# io2.net
KiCad netlist of a schematic drawn in EAGLE
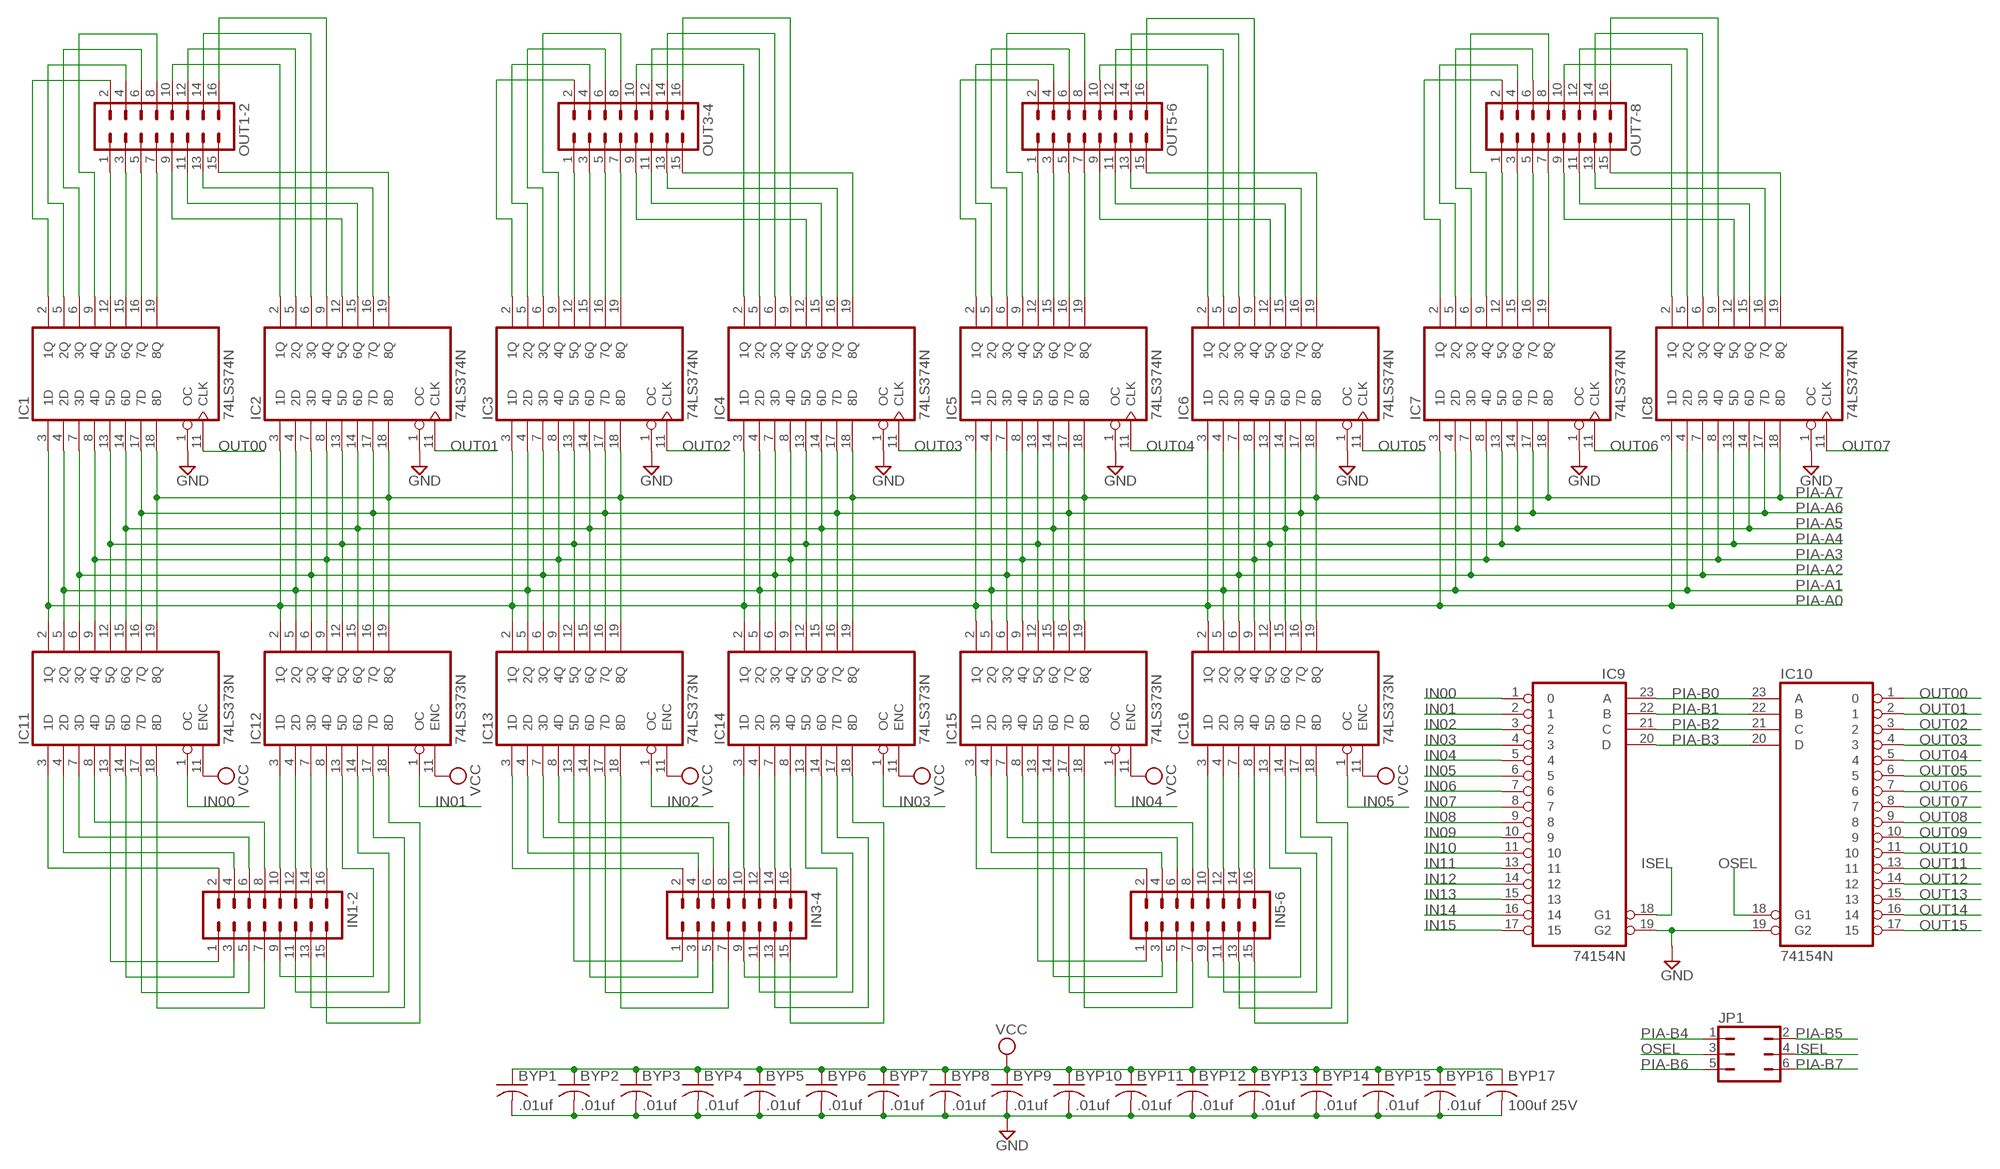
[diagram p0: schematic, sheet 1]
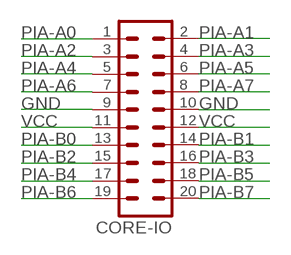
[diagram p1: schematic, sheet 2]

(export (version "E")
  (design (tool "Eeschema 10.0.6"))
  (components
    (comp (ref "CORE-IO")
      (value "MA10-2")
      (footprint "eagle-import:MA10-2")
      (libsource (lib "eagle-import") (part "MA10-2"))
    )
    (comp (ref "BYP1")
      (value ".01uf")
      (footprint "eagle-import:C050-025X075")
      (libsource (lib "eagle-import") (part "C-US050-025X075"))
    )
    (comp (ref "BYP2")
      (value ".01uf")
      (footprint "eagle-import:C050-025X075")
      (libsource (lib "eagle-import") (part "C-US050-025X075"))
    )
    (comp (ref "BYP3")
      (value ".01uf")
      (footprint "eagle-import:C050-025X075")
      (libsource (lib "eagle-import") (part "C-US050-025X075"))
    )
    (comp (ref "BYP4")
      (value ".01uf")
      (footprint "eagle-import:C050-025X075")
      (libsource (lib "eagle-import") (part "C-US050-025X075"))
    )
    (comp (ref "BYP5")
      (value ".01uf")
      (footprint "eagle-import:C050-025X075")
      (libsource (lib "eagle-import") (part "C-US050-025X075"))
    )
    (comp (ref "BYP6")
      (value ".01uf")
      (footprint "eagle-import:C050-025X075")
      (libsource (lib "eagle-import") (part "C-US050-025X075"))
    )
    (comp (ref "BYP7")
      (value ".01uf")
      (footprint "eagle-import:C050-025X075")
      (libsource (lib "eagle-import") (part "C-US050-025X075"))
    )
    (comp (ref "BYP8")
      (value ".01uf")
      (footprint "eagle-import:C050-025X075")
      (libsource (lib "eagle-import") (part "C-US050-025X075"))
    )
    (comp (ref "BYP9")
      (value ".01uf")
      (footprint "eagle-import:C050-025X075")
      (libsource (lib "eagle-import") (part "C-US050-025X075"))
    )
    (comp (ref "BYP10")
      (value ".01uf")
      (footprint "eagle-import:C050-025X075")
      (libsource (lib "eagle-import") (part "C-US050-025X075"))
    )
    (comp (ref "BYP11")
      (value ".01uf")
      (footprint "eagle-import:C050-025X075")
      (libsource (lib "eagle-import") (part "C-US050-025X075"))
    )
    (comp (ref "BYP12")
      (value ".01uf")
      (footprint "eagle-import:C050-025X075")
      (libsource (lib "eagle-import") (part "C-US050-025X075"))
    )
    (comp (ref "BYP13")
      (value ".01uf")
      (footprint "eagle-import:C050-025X075")
      (libsource (lib "eagle-import") (part "C-US050-025X075"))
    )
    (comp (ref "BYP14")
      (value ".01uf")
      (footprint "eagle-import:C050-025X075")
      (libsource (lib "eagle-import") (part "C-US050-025X075"))
    )
    (comp (ref "BYP15")
      (value ".01uf")
      (footprint "eagle-import:C050-025X075")
      (libsource (lib "eagle-import") (part "C-US050-025X075"))
    )
    (comp (ref "BYP16")
      (value ".01uf")
      (footprint "eagle-import:C050-025X075")
      (libsource (lib "eagle-import") (part "C-US050-025X075"))
    )
    (comp (ref "BYP17")
      (value "100uf 25V")
      (footprint "eagle-import:C102-043X133")
      (libsource (lib "eagle-import") (part "C-US102-043X133"))
    )
    (comp (ref "IC1")
      (value "74LS374N")
      (footprint "eagle-import:DIL20")
      (libsource (lib "eagle-import") (part "74374NLS"))
    )
    (comp (ref "IC2")
      (value "74LS374N")
      (footprint "eagle-import:DIL20")
      (libsource (lib "eagle-import") (part "74374NLS"))
    )
    (comp (ref "IC3")
      (value "74LS374N")
      (footprint "eagle-import:DIL20")
      (libsource (lib "eagle-import") (part "74374NLS"))
    )
    (comp (ref "IC4")
      (value "74LS374N")
      (footprint "eagle-import:DIL20")
      (libsource (lib "eagle-import") (part "74374NLS"))
    )
    (comp (ref "IC5")
      (value "74LS374N")
      (footprint "eagle-import:DIL20")
      (libsource (lib "eagle-import") (part "74374NLS"))
    )
    (comp (ref "IC6")
      (value "74LS374N")
      (footprint "eagle-import:DIL20")
      (libsource (lib "eagle-import") (part "74374NLS"))
    )
    (comp (ref "IC7")
      (value "74LS374N")
      (footprint "eagle-import:DIL20")
      (libsource (lib "eagle-import") (part "74374NLS"))
    )
    (comp (ref "IC8")
      (value "74LS374N")
      (footprint "eagle-import:DIL20")
      (libsource (lib "eagle-import") (part "74374NLS"))
    )
    (comp (ref "IC9")
      (value "74154N")
      (footprint "eagle-import:DIL24-6")
      (libsource (lib "eagle-import") (part "74154N"))
    )
    (comp (ref "IC10")
      (value "74154N")
      (footprint "eagle-import:DIL24-6")
      (libsource (lib "eagle-import") (part "74154N"))
    )
    (comp (ref "IC11")
      (value "74LS373N")
      (footprint "eagle-import:DIL20")
      (libsource (lib "eagle-import") (part "74373NLS"))
    )
    (comp (ref "IC12")
      (value "74LS373N")
      (footprint "eagle-import:DIL20")
      (libsource (lib "eagle-import") (part "74373NLS"))
    )
    (comp (ref "IC13")
      (value "74LS373N")
      (footprint "eagle-import:DIL20")
      (libsource (lib "eagle-import") (part "74373NLS"))
    )
    (comp (ref "IC14")
      (value "74LS373N")
      (footprint "eagle-import:DIL20")
      (libsource (lib "eagle-import") (part "74373NLS"))
    )
    (comp (ref "IC15")
      (value "74LS373N")
      (footprint "eagle-import:DIL20")
      (libsource (lib "eagle-import") (part "74373NLS"))
    )
    (comp (ref "IC16")
      (value "74LS373N")
      (footprint "eagle-import:DIL20")
      (libsource (lib "eagle-import") (part "74373NLS"))
    )
    (comp (ref "IN1-2")
      (value "MA08-2")
      (footprint "eagle-import:MA08-2")
      (libsource (lib "eagle-import") (part "MA08-2"))
    )
    (comp (ref "IN3-4")
      (value "MA08-2")
      (footprint "eagle-import:MA08-2")
      (libsource (lib "eagle-import") (part "MA08-2"))
    )
    (comp (ref "IN5-6")
      (value "MA08-2")
      (footprint "eagle-import:MA08-2")
      (libsource (lib "eagle-import") (part "MA08-2"))
    )
    (comp (ref "JP1")
      (value "JP3Q")
      (footprint "eagle-import:JP3Q")
      (libsource (lib "eagle-import") (part "JP3Q"))
    )
    (comp (ref "OUT1-2")
      (value "MA08-2")
      (footprint "eagle-import:MA08-2")
      (libsource (lib "eagle-import") (part "MA08-2"))
    )
    (comp (ref "OUT3-4")
      (value "MA08-2")
      (footprint "eagle-import:MA08-2")
      (libsource (lib "eagle-import") (part "MA08-2"))
    )
    (comp (ref "OUT5-6")
      (value "MA08-2")
      (footprint "eagle-import:MA08-2")
      (libsource (lib "eagle-import") (part "MA08-2"))
    )
    (comp (ref "OUT7-8")
      (value "MA08-2")
      (footprint "eagle-import:MA08-2")
      (libsource (lib "eagle-import") (part "MA08-2"))
    )
  )
  (nets
    (net (code "1") (name "GND") (class "Default")
      (node (ref "BYP1") (pin "2") (pinfunction "2_2") (pintype "passive"))
      (node (ref "BYP10") (pin "2") (pinfunction "2_2") (pintype "passive"))
      (node (ref "BYP11") (pin "2") (pinfunction "2_2") (pintype "passive"))
      (node (ref "BYP12") (pin "2") (pinfunction "2_2") (pintype "passive"))
      (node (ref "BYP13") (pin "2") (pinfunction "2_2") (pintype "passive"))
      (node (ref "BYP14") (pin "2") (pinfunction "2_2") (pintype "passive"))
      (node (ref "BYP15") (pin "2") (pinfunction "2_2") (pintype "passive"))
      (node (ref "BYP16") (pin "2") (pinfunction "2_2") (pintype "passive"))
      (node (ref "BYP17") (pin "2") (pinfunction "2_2") (pintype "passive"))
      (node (ref "BYP2") (pin "2") (pinfunction "2_2") (pintype "passive"))
      (node (ref "BYP3") (pin "2") (pinfunction "2_2") (pintype "passive"))
      (node (ref "BYP4") (pin "2") (pinfunction "2_2") (pintype "passive"))
      (node (ref "BYP5") (pin "2") (pinfunction "2_2") (pintype "passive"))
      (node (ref "BYP6") (pin "2") (pinfunction "2_2") (pintype "passive"))
      (node (ref "BYP7") (pin "2") (pinfunction "2_2") (pintype "passive"))
      (node (ref "BYP8") (pin "2") (pinfunction "2_2") (pintype "passive"))
      (node (ref "BYP9") (pin "2") (pinfunction "2_2") (pintype "passive"))
      (node (ref "CORE-IO") (pin "10") (pinfunction "10_10") (pintype "passive"))
      (node (ref "CORE-IO") (pin "9") (pinfunction "9_9") (pintype "passive"))
      (node (ref "IC1") (pin "1") (pinfunction "OC_1") (pintype "input"))
      (node (ref "IC10") (pin "19") (pinfunction "G2_19") (pintype "input"))
      (node (ref "IC2") (pin "1") (pinfunction "OC_1") (pintype "input"))
      (node (ref "IC3") (pin "1") (pinfunction "OC_1") (pintype "input"))
      (node (ref "IC4") (pin "1") (pinfunction "OC_1") (pintype "input"))
      (node (ref "IC5") (pin "1") (pinfunction "OC_1") (pintype "input"))
      (node (ref "IC6") (pin "1") (pinfunction "OC_1") (pintype "input"))
      (node (ref "IC7") (pin "1") (pinfunction "OC_1") (pintype "input"))
      (node (ref "IC8") (pin "1") (pinfunction "OC_1") (pintype "input"))
      (node (ref "IC9") (pin "19") (pinfunction "G2_19") (pintype "input"))
    )
    (net (code "2") (name "IN00") (class "Default")
      (node (ref "IC11") (pin "1") (pinfunction "OC_1") (pintype "input"))
      (node (ref "IC9") (pin "1") (pinfunction "0_1") (pintype "output"))
    )
    (net (code "3") (name "IN01") (class "Default")
      (node (ref "IC12") (pin "1") (pinfunction "OC_1") (pintype "input"))
      (node (ref "IC9") (pin "2") (pinfunction "1_2") (pintype "output"))
    )
    (net (code "4") (name "IN02") (class "Default")
      (node (ref "IC13") (pin "1") (pinfunction "OC_1") (pintype "input"))
      (node (ref "IC9") (pin "3") (pinfunction "2_3") (pintype "output"))
    )
    (net (code "5") (name "IN03") (class "Default")
      (node (ref "IC14") (pin "1") (pinfunction "OC_1") (pintype "input"))
      (node (ref "IC9") (pin "4") (pinfunction "3_4") (pintype "output"))
    )
    (net (code "6") (name "IN04") (class "Default")
      (node (ref "IC15") (pin "1") (pinfunction "OC_1") (pintype "input"))
      (node (ref "IC9") (pin "5") (pinfunction "4_5") (pintype "output"))
    )
    (net (code "7") (name "IN05") (class "Default")
      (node (ref "IC16") (pin "1") (pinfunction "OC_1") (pintype "input"))
      (node (ref "IC9") (pin "6") (pinfunction "5_6") (pintype "output"))
    )
    (net (code "8") (name "IN06") (class "Default")
      (node (ref "IC9") (pin "7") (pinfunction "6_7") (pintype "output"))
    )
    (net (code "9") (name "IN07") (class "Default")
      (node (ref "IC9") (pin "8") (pinfunction "7_8") (pintype "output"))
    )
    (net (code "10") (name "IN08") (class "Default")
      (node (ref "IC9") (pin "9") (pinfunction "8_9") (pintype "output"))
    )
    (net (code "11") (name "IN09") (class "Default")
      (node (ref "IC9") (pin "10") (pinfunction "9_10") (pintype "output"))
    )
    (net (code "12") (name "IN10") (class "Default")
      (node (ref "IC9") (pin "11") (pinfunction "10_11") (pintype "output"))
    )
    (net (code "13") (name "IN11") (class "Default")
      (node (ref "IC9") (pin "13") (pinfunction "11_13") (pintype "output"))
    )
    (net (code "14") (name "IN12") (class "Default")
      (node (ref "IC9") (pin "14") (pinfunction "12_14") (pintype "output"))
    )
    (net (code "15") (name "IN13") (class "Default")
      (node (ref "IC9") (pin "15") (pinfunction "13_15") (pintype "output"))
    )
    (net (code "16") (name "IN14") (class "Default")
      (node (ref "IC9") (pin "16") (pinfunction "14_16") (pintype "output"))
    )
    (net (code "17") (name "IN15") (class "Default")
      (node (ref "IC9") (pin "17") (pinfunction "15_17") (pintype "output"))
    )
    (net (code "18") (name "ISEL") (class "Default")
      (node (ref "IC9") (pin "18") (pinfunction "G1_18") (pintype "input"))
      (node (ref "JP1") (pin "4") (pinfunction "4_4") (pintype "passive"))
    )
    (net (code "19") (name "Net-(IC1A-1Q)") (class "Default")
      (node (ref "IC1") (pin "2") (pinfunction "1Q_2") (pintype "tri_state"))
      (node (ref "OUT1-2") (pin "2") (pinfunction "2_2") (pintype "passive"))
    )
    (net (code "20") (name "Net-(IC1A-2Q)") (class "Default")
      (node (ref "IC1") (pin "5") (pinfunction "2Q_5") (pintype "tri_state"))
      (node (ref "OUT1-2") (pin "4") (pinfunction "4_4") (pintype "passive"))
    )
    (net (code "21") (name "Net-(IC1A-3Q)") (class "Default")
      (node (ref "IC1") (pin "6") (pinfunction "3Q_6") (pintype "tri_state"))
      (node (ref "OUT1-2") (pin "6") (pinfunction "6_6") (pintype "passive"))
    )
    (net (code "22") (name "Net-(IC1A-4Q)") (class "Default")
      (node (ref "IC1") (pin "9") (pinfunction "4Q_9") (pintype "tri_state"))
      (node (ref "OUT1-2") (pin "8") (pinfunction "8_8") (pintype "passive"))
    )
    (net (code "23") (name "Net-(IC1A-5Q)") (class "Default")
      (node (ref "IC1") (pin "12") (pinfunction "5Q_12") (pintype "tri_state"))
      (node (ref "OUT1-2") (pin "1") (pinfunction "1_1") (pintype "passive"))
    )
    (net (code "24") (name "Net-(IC1A-6Q)") (class "Default")
      (node (ref "IC1") (pin "15") (pinfunction "6Q_15") (pintype "tri_state"))
      (node (ref "OUT1-2") (pin "3") (pinfunction "3_3") (pintype "passive"))
    )
    (net (code "25") (name "Net-(IC1A-7Q)") (class "Default")
      (node (ref "IC1") (pin "16") (pinfunction "7Q_16") (pintype "tri_state"))
      (node (ref "OUT1-2") (pin "5") (pinfunction "5_5") (pintype "passive"))
    )
    (net (code "26") (name "Net-(IC1A-8Q)") (class "Default")
      (node (ref "IC1") (pin "19") (pinfunction "8Q_19") (pintype "tri_state"))
      (node (ref "OUT1-2") (pin "7") (pinfunction "7_7") (pintype "passive"))
    )
    (net (code "27") (name "Net-(IC2A-1Q)") (class "Default")
      (node (ref "IC2") (pin "2") (pinfunction "1Q_2") (pintype "tri_state"))
      (node (ref "OUT1-2") (pin "10") (pinfunction "10_10") (pintype "passive"))
    )
    (net (code "28") (name "Net-(IC2A-2Q)") (class "Default")
      (node (ref "IC2") (pin "5") (pinfunction "2Q_5") (pintype "tri_state"))
      (node (ref "OUT1-2") (pin "12") (pinfunction "12_12") (pintype "passive"))
    )
    (net (code "29") (name "Net-(IC2A-3Q)") (class "Default")
      (node (ref "IC2") (pin "6") (pinfunction "3Q_6") (pintype "tri_state"))
      (node (ref "OUT1-2") (pin "14") (pinfunction "14_14") (pintype "passive"))
    )
    (net (code "30") (name "Net-(IC2A-4Q)") (class "Default")
      (node (ref "IC2") (pin "9") (pinfunction "4Q_9") (pintype "tri_state"))
      (node (ref "OUT1-2") (pin "16") (pinfunction "16_16") (pintype "passive"))
    )
    (net (code "31") (name "Net-(IC2A-5Q)") (class "Default")
      (node (ref "IC2") (pin "12") (pinfunction "5Q_12") (pintype "tri_state"))
      (node (ref "OUT1-2") (pin "9") (pinfunction "9_9") (pintype "passive"))
    )
    (net (code "32") (name "Net-(IC2A-6Q)") (class "Default")
      (node (ref "IC2") (pin "15") (pinfunction "6Q_15") (pintype "tri_state"))
      (node (ref "OUT1-2") (pin "11") (pinfunction "11_11") (pintype "passive"))
    )
    (net (code "33") (name "Net-(IC2A-7Q)") (class "Default")
      (node (ref "IC2") (pin "16") (pinfunction "7Q_16") (pintype "tri_state"))
      (node (ref "OUT1-2") (pin "13") (pinfunction "13_13") (pintype "passive"))
    )
    (net (code "34") (name "Net-(IC2A-8Q)") (class "Default")
      (node (ref "IC2") (pin "19") (pinfunction "8Q_19") (pintype "tri_state"))
      (node (ref "OUT1-2") (pin "15") (pinfunction "15_15") (pintype "passive"))
    )
    (net (code "35") (name "Net-(IC3A-1Q)") (class "Default")
      (node (ref "IC3") (pin "2") (pinfunction "1Q_2") (pintype "tri_state"))
      (node (ref "OUT3-4") (pin "2") (pinfunction "2_2") (pintype "passive"))
    )
    (net (code "36") (name "Net-(IC3A-2Q)") (class "Default")
      (node (ref "IC3") (pin "5") (pinfunction "2Q_5") (pintype "tri_state"))
      (node (ref "OUT3-4") (pin "4") (pinfunction "4_4") (pintype "passive"))
    )
    (net (code "37") (name "Net-(IC3A-3Q)") (class "Default")
      (node (ref "IC3") (pin "6") (pinfunction "3Q_6") (pintype "tri_state"))
      (node (ref "OUT3-4") (pin "6") (pinfunction "6_6") (pintype "passive"))
    )
    (net (code "38") (name "Net-(IC3A-4Q)") (class "Default")
      (node (ref "IC3") (pin "9") (pinfunction "4Q_9") (pintype "tri_state"))
      (node (ref "OUT3-4") (pin "8") (pinfunction "8_8") (pintype "passive"))
    )
    (net (code "39") (name "Net-(IC3A-5Q)") (class "Default")
      (node (ref "IC3") (pin "12") (pinfunction "5Q_12") (pintype "tri_state"))
      (node (ref "OUT3-4") (pin "1") (pinfunction "1_1") (pintype "passive"))
    )
    (net (code "40") (name "Net-(IC3A-6Q)") (class "Default")
      (node (ref "IC3") (pin "15") (pinfunction "6Q_15") (pintype "tri_state"))
      (node (ref "OUT3-4") (pin "3") (pinfunction "3_3") (pintype "passive"))
    )
    (net (code "41") (name "Net-(IC3A-7Q)") (class "Default")
      (node (ref "IC3") (pin "16") (pinfunction "7Q_16") (pintype "tri_state"))
      (node (ref "OUT3-4") (pin "5") (pinfunction "5_5") (pintype "passive"))
    )
    (net (code "42") (name "Net-(IC3A-8Q)") (class "Default")
      (node (ref "IC3") (pin "19") (pinfunction "8Q_19") (pintype "tri_state"))
      (node (ref "OUT3-4") (pin "7") (pinfunction "7_7") (pintype "passive"))
    )
    (net (code "43") (name "Net-(IC4A-1Q)") (class "Default")
      (node (ref "IC4") (pin "2") (pinfunction "1Q_2") (pintype "tri_state"))
      (node (ref "OUT3-4") (pin "10") (pinfunction "10_10") (pintype "passive"))
    )
    (net (code "44") (name "Net-(IC4A-2Q)") (class "Default")
      (node (ref "IC4") (pin "5") (pinfunction "2Q_5") (pintype "tri_state"))
      (node (ref "OUT3-4") (pin "12") (pinfunction "12_12") (pintype "passive"))
    )
    (net (code "45") (name "Net-(IC4A-3Q)") (class "Default")
      (node (ref "IC4") (pin "6") (pinfunction "3Q_6") (pintype "tri_state"))
      (node (ref "OUT3-4") (pin "14") (pinfunction "14_14") (pintype "passive"))
    )
    (net (code "46") (name "Net-(IC4A-4Q)") (class "Default")
      (node (ref "IC4") (pin "9") (pinfunction "4Q_9") (pintype "tri_state"))
      (node (ref "OUT3-4") (pin "16") (pinfunction "16_16") (pintype "passive"))
    )
    (net (code "47") (name "Net-(IC4A-5Q)") (class "Default")
      (node (ref "IC4") (pin "12") (pinfunction "5Q_12") (pintype "tri_state"))
      (node (ref "OUT3-4") (pin "9") (pinfunction "9_9") (pintype "passive"))
    )
    (net (code "48") (name "Net-(IC4A-6Q)") (class "Default")
      (node (ref "IC4") (pin "15") (pinfunction "6Q_15") (pintype "tri_state"))
      (node (ref "OUT3-4") (pin "11") (pinfunction "11_11") (pintype "passive"))
    )
    (net (code "49") (name "Net-(IC4A-7Q)") (class "Default")
      (node (ref "IC4") (pin "16") (pinfunction "7Q_16") (pintype "tri_state"))
      (node (ref "OUT3-4") (pin "13") (pinfunction "13_13") (pintype "passive"))
    )
    (net (code "50") (name "Net-(IC4A-8Q)") (class "Default")
      (node (ref "IC4") (pin "19") (pinfunction "8Q_19") (pintype "tri_state"))
      (node (ref "OUT3-4") (pin "15") (pinfunction "15_15") (pintype "passive"))
    )
    (net (code "51") (name "Net-(IC5A-1Q)") (class "Default")
      (node (ref "IC5") (pin "2") (pinfunction "1Q_2") (pintype "tri_state"))
      (node (ref "OUT5-6") (pin "2") (pinfunction "2_2") (pintype "passive"))
    )
    (net (code "52") (name "Net-(IC5A-2Q)") (class "Default")
      (node (ref "IC5") (pin "5") (pinfunction "2Q_5") (pintype "tri_state"))
      (node (ref "OUT5-6") (pin "4") (pinfunction "4_4") (pintype "passive"))
    )
    (net (code "53") (name "Net-(IC5A-3Q)") (class "Default")
      (node (ref "IC5") (pin "6") (pinfunction "3Q_6") (pintype "tri_state"))
      (node (ref "OUT5-6") (pin "6") (pinfunction "6_6") (pintype "passive"))
    )
    (net (code "54") (name "Net-(IC5A-4Q)") (class "Default")
      (node (ref "IC5") (pin "9") (pinfunction "4Q_9") (pintype "tri_state"))
      (node (ref "OUT5-6") (pin "8") (pinfunction "8_8") (pintype "passive"))
    )
    (net (code "55") (name "Net-(IC5A-5Q)") (class "Default")
      (node (ref "IC5") (pin "12") (pinfunction "5Q_12") (pintype "tri_state"))
      (node (ref "OUT5-6") (pin "1") (pinfunction "1_1") (pintype "passive"))
    )
    (net (code "56") (name "Net-(IC5A-6Q)") (class "Default")
      (node (ref "IC5") (pin "15") (pinfunction "6Q_15") (pintype "tri_state"))
      (node (ref "OUT5-6") (pin "3") (pinfunction "3_3") (pintype "passive"))
    )
    (net (code "57") (name "Net-(IC5A-7Q)") (class "Default")
      (node (ref "IC5") (pin "16") (pinfunction "7Q_16") (pintype "tri_state"))
      (node (ref "OUT5-6") (pin "5") (pinfunction "5_5") (pintype "passive"))
    )
    (net (code "58") (name "Net-(IC5A-8Q)") (class "Default")
      (node (ref "IC5") (pin "19") (pinfunction "8Q_19") (pintype "tri_state"))
      (node (ref "OUT5-6") (pin "7") (pinfunction "7_7") (pintype "passive"))
    )
    (net (code "59") (name "Net-(IC6A-1Q)") (class "Default")
      (node (ref "IC6") (pin "2") (pinfunction "1Q_2") (pintype "tri_state"))
      (node (ref "OUT5-6") (pin "10") (pinfunction "10_10") (pintype "passive"))
    )
    (net (code "60") (name "Net-(IC6A-2Q)") (class "Default")
      (node (ref "IC6") (pin "5") (pinfunction "2Q_5") (pintype "tri_state"))
      (node (ref "OUT5-6") (pin "12") (pinfunction "12_12") (pintype "passive"))
    )
    (net (code "61") (name "Net-(IC6A-3Q)") (class "Default")
      (node (ref "IC6") (pin "6") (pinfunction "3Q_6") (pintype "tri_state"))
      (node (ref "OUT5-6") (pin "14") (pinfunction "14_14") (pintype "passive"))
    )
    (net (code "62") (name "Net-(IC6A-4Q)") (class "Default")
      (node (ref "IC6") (pin "9") (pinfunction "4Q_9") (pintype "tri_state"))
      (node (ref "OUT5-6") (pin "16") (pinfunction "16_16") (pintype "passive"))
    )
    (net (code "63") (name "Net-(IC6A-5Q)") (class "Default")
      (node (ref "IC6") (pin "12") (pinfunction "5Q_12") (pintype "tri_state"))
      (node (ref "OUT5-6") (pin "9") (pinfunction "9_9") (pintype "passive"))
    )
    (net (code "64") (name "Net-(IC6A-6Q)") (class "Default")
      (node (ref "IC6") (pin "15") (pinfunction "6Q_15") (pintype "tri_state"))
      (node (ref "OUT5-6") (pin "11") (pinfunction "11_11") (pintype "passive"))
    )
    (net (code "65") (name "Net-(IC6A-7Q)") (class "Default")
      (node (ref "IC6") (pin "16") (pinfunction "7Q_16") (pintype "tri_state"))
      (node (ref "OUT5-6") (pin "13") (pinfunction "13_13") (pintype "passive"))
    )
    (net (code "66") (name "Net-(IC6A-8Q)") (class "Default")
      (node (ref "IC6") (pin "19") (pinfunction "8Q_19") (pintype "tri_state"))
      (node (ref "OUT5-6") (pin "15") (pinfunction "15_15") (pintype "passive"))
    )
    (net (code "67") (name "Net-(IC7A-1Q)") (class "Default")
      (node (ref "IC7") (pin "2") (pinfunction "1Q_2") (pintype "tri_state"))
      (node (ref "OUT7-8") (pin "2") (pinfunction "2_2") (pintype "passive"))
    )
    (net (code "68") (name "Net-(IC7A-2Q)") (class "Default")
      (node (ref "IC7") (pin "5") (pinfunction "2Q_5") (pintype "tri_state"))
      (node (ref "OUT7-8") (pin "4") (pinfunction "4_4") (pintype "passive"))
    )
    (net (code "69") (name "Net-(IC7A-3Q)") (class "Default")
      (node (ref "IC7") (pin "6") (pinfunction "3Q_6") (pintype "tri_state"))
      (node (ref "OUT7-8") (pin "6") (pinfunction "6_6") (pintype "passive"))
    )
    (net (code "70") (name "Net-(IC7A-4Q)") (class "Default")
      (node (ref "IC7") (pin "9") (pinfunction "4Q_9") (pintype "tri_state"))
      (node (ref "OUT7-8") (pin "8") (pinfunction "8_8") (pintype "passive"))
    )
    (net (code "71") (name "Net-(IC7A-5Q)") (class "Default")
      (node (ref "IC7") (pin "12") (pinfunction "5Q_12") (pintype "tri_state"))
      (node (ref "OUT7-8") (pin "1") (pinfunction "1_1") (pintype "passive"))
    )
    (net (code "72") (name "Net-(IC7A-6Q)") (class "Default")
      (node (ref "IC7") (pin "15") (pinfunction "6Q_15") (pintype "tri_state"))
      (node (ref "OUT7-8") (pin "3") (pinfunction "3_3") (pintype "passive"))
    )
    (net (code "73") (name "Net-(IC7A-7Q)") (class "Default")
      (node (ref "IC7") (pin "16") (pinfunction "7Q_16") (pintype "tri_state"))
      (node (ref "OUT7-8") (pin "5") (pinfunction "5_5") (pintype "passive"))
    )
    (net (code "74") (name "Net-(IC7A-8Q)") (class "Default")
      (node (ref "IC7") (pin "19") (pinfunction "8Q_19") (pintype "tri_state"))
      (node (ref "OUT7-8") (pin "7") (pinfunction "7_7") (pintype "passive"))
    )
    (net (code "75") (name "Net-(IC8A-1Q)") (class "Default")
      (node (ref "IC8") (pin "2") (pinfunction "1Q_2") (pintype "tri_state"))
      (node (ref "OUT7-8") (pin "10") (pinfunction "10_10") (pintype "passive"))
    )
    (net (code "76") (name "Net-(IC8A-2Q)") (class "Default")
      (node (ref "IC8") (pin "5") (pinfunction "2Q_5") (pintype "tri_state"))
      (node (ref "OUT7-8") (pin "12") (pinfunction "12_12") (pintype "passive"))
    )
    (net (code "77") (name "Net-(IC8A-3Q)") (class "Default")
      (node (ref "IC8") (pin "6") (pinfunction "3Q_6") (pintype "tri_state"))
      (node (ref "OUT7-8") (pin "14") (pinfunction "14_14") (pintype "passive"))
    )
    (net (code "78") (name "Net-(IC8A-4Q)") (class "Default")
      (node (ref "IC8") (pin "9") (pinfunction "4Q_9") (pintype "tri_state"))
      (node (ref "OUT7-8") (pin "16") (pinfunction "16_16") (pintype "passive"))
    )
    (net (code "79") (name "Net-(IC8A-5Q)") (class "Default")
      (node (ref "IC8") (pin "12") (pinfunction "5Q_12") (pintype "tri_state"))
      (node (ref "OUT7-8") (pin "9") (pinfunction "9_9") (pintype "passive"))
    )
    (net (code "80") (name "Net-(IC8A-6Q)") (class "Default")
      (node (ref "IC8") (pin "15") (pinfunction "6Q_15") (pintype "tri_state"))
      (node (ref "OUT7-8") (pin "11") (pinfunction "11_11") (pintype "passive"))
    )
    (net (code "81") (name "Net-(IC8A-7Q)") (class "Default")
      (node (ref "IC8") (pin "16") (pinfunction "7Q_16") (pintype "tri_state"))
      (node (ref "OUT7-8") (pin "13") (pinfunction "13_13") (pintype "passive"))
    )
    (net (code "82") (name "Net-(IC8A-8Q)") (class "Default")
      (node (ref "IC8") (pin "19") (pinfunction "8Q_19") (pintype "tri_state"))
      (node (ref "OUT7-8") (pin "15") (pinfunction "15_15") (pintype "passive"))
    )
    (net (code "83") (name "Net-(IC11A-1D)") (class "Default")
      (node (ref "IC11") (pin "3") (pinfunction "1D_3") (pintype "input"))
      (node (ref "IN1-2") (pin "2") (pinfunction "2_2") (pintype "passive"))
    )
    (net (code "84") (name "Net-(IC11A-2D)") (class "Default")
      (node (ref "IC11") (pin "4") (pinfunction "2D_4") (pintype "input"))
      (node (ref "IN1-2") (pin "4") (pinfunction "4_4") (pintype "passive"))
    )
    (net (code "85") (name "Net-(IC11A-3D)") (class "Default")
      (node (ref "IC11") (pin "7") (pinfunction "3D_7") (pintype "input"))
      (node (ref "IN1-2") (pin "6") (pinfunction "6_6") (pintype "passive"))
    )
    (net (code "86") (name "Net-(IC11A-4D)") (class "Default")
      (node (ref "IC11") (pin "8") (pinfunction "4D_8") (pintype "input"))
      (node (ref "IN1-2") (pin "8") (pinfunction "8_8") (pintype "passive"))
    )
    (net (code "87") (name "Net-(IC11A-5D)") (class "Default")
      (node (ref "IC11") (pin "13") (pinfunction "5D_13") (pintype "input"))
      (node (ref "IN1-2") (pin "1") (pinfunction "1_1") (pintype "passive"))
    )
    (net (code "88") (name "Net-(IC11A-6D)") (class "Default")
      (node (ref "IC11") (pin "14") (pinfunction "6D_14") (pintype "input"))
      (node (ref "IN1-2") (pin "3") (pinfunction "3_3") (pintype "passive"))
    )
    (net (code "89") (name "Net-(IC11A-7D)") (class "Default")
      (node (ref "IC11") (pin "17") (pinfunction "7D_17") (pintype "input"))
      (node (ref "IN1-2") (pin "5") (pinfunction "5_5") (pintype "passive"))
    )
    (net (code "90") (name "Net-(IC11A-8D)") (class "Default")
      (node (ref "IC11") (pin "18") (pinfunction "8D_18") (pintype "input"))
      (node (ref "IN1-2") (pin "7") (pinfunction "7_7") (pintype "passive"))
    )
    (net (code "91") (name "Net-(IC12A-1D)") (class "Default")
      (node (ref "IC12") (pin "3") (pinfunction "1D_3") (pintype "input"))
      (node (ref "IN1-2") (pin "10") (pinfunction "10_10") (pintype "passive"))
    )
    (net (code "92") (name "Net-(IC12A-2D)") (class "Default")
      (node (ref "IC12") (pin "4") (pinfunction "2D_4") (pintype "input"))
      (node (ref "IN1-2") (pin "12") (pinfunction "12_12") (pintype "passive"))
    )
    (net (code "93") (name "Net-(IC12A-3D)") (class "Default")
      (node (ref "IC12") (pin "7") (pinfunction "3D_7") (pintype "input"))
      (node (ref "IN1-2") (pin "14") (pinfunction "14_14") (pintype "passive"))
    )
    (net (code "94") (name "Net-(IC12A-4D)") (class "Default")
      (node (ref "IC12") (pin "8") (pinfunction "4D_8") (pintype "input"))
      (node (ref "IN1-2") (pin "16") (pinfunction "16_16") (pintype "passive"))
    )
    (net (code "95") (name "Net-(IC12A-5D)") (class "Default")
      (node (ref "IC12") (pin "13") (pinfunction "5D_13") (pintype "input"))
      (node (ref "IN1-2") (pin "9") (pinfunction "9_9") (pintype "passive"))
    )
    (net (code "96") (name "Net-(IC12A-6D)") (class "Default")
      (node (ref "IC12") (pin "14") (pinfunction "6D_14") (pintype "input"))
      (node (ref "IN1-2") (pin "11") (pinfunction "11_11") (pintype "passive"))
    )
    (net (code "97") (name "Net-(IC12A-7D)") (class "Default")
      (node (ref "IC12") (pin "17") (pinfunction "7D_17") (pintype "input"))
      (node (ref "IN1-2") (pin "13") (pinfunction "13_13") (pintype "passive"))
    )
    (net (code "98") (name "Net-(IC12A-8D)") (class "Default")
      (node (ref "IC12") (pin "18") (pinfunction "8D_18") (pintype "input"))
      (node (ref "IN1-2") (pin "15") (pinfunction "15_15") (pintype "passive"))
    )
    (net (code "99") (name "Net-(IC13A-1D)") (class "Default")
      (node (ref "IC13") (pin "3") (pinfunction "1D_3") (pintype "input"))
      (node (ref "IN3-4") (pin "2") (pinfunction "2_2") (pintype "passive"))
    )
    (net (code "100") (name "Net-(IC13A-2D)") (class "Default")
      (node (ref "IC13") (pin "4") (pinfunction "2D_4") (pintype "input"))
      (node (ref "IN3-4") (pin "4") (pinfunction "4_4") (pintype "passive"))
    )
    (net (code "101") (name "Net-(IC13A-3D)") (class "Default")
      (node (ref "IC13") (pin "7") (pinfunction "3D_7") (pintype "input"))
      (node (ref "IN3-4") (pin "6") (pinfunction "6_6") (pintype "passive"))
    )
    (net (code "102") (name "Net-(IC13A-4D)") (class "Default")
      (node (ref "IC13") (pin "8") (pinfunction "4D_8") (pintype "input"))
      (node (ref "IN3-4") (pin "8") (pinfunction "8_8") (pintype "passive"))
    )
    (net (code "103") (name "Net-(IC13A-5D)") (class "Default")
      (node (ref "IC13") (pin "13") (pinfunction "5D_13") (pintype "input"))
      (node (ref "IN3-4") (pin "1") (pinfunction "1_1") (pintype "passive"))
    )
    (net (code "104") (name "Net-(IC13A-6D)") (class "Default")
      (node (ref "IC13") (pin "14") (pinfunction "6D_14") (pintype "input"))
      (node (ref "IN3-4") (pin "3") (pinfunction "3_3") (pintype "passive"))
    )
    (net (code "105") (name "Net-(IC13A-7D)") (class "Default")
      (node (ref "IC13") (pin "17") (pinfunction "7D_17") (pintype "input"))
      (node (ref "IN3-4") (pin "5") (pinfunction "5_5") (pintype "passive"))
    )
    (net (code "106") (name "Net-(IC13A-8D)") (class "Default")
      (node (ref "IC13") (pin "18") (pinfunction "8D_18") (pintype "input"))
      (node (ref "IN3-4") (pin "7") (pinfunction "7_7") (pintype "passive"))
    )
    (net (code "107") (name "Net-(IC14A-1D)") (class "Default")
      (node (ref "IC14") (pin "3") (pinfunction "1D_3") (pintype "input"))
      (node (ref "IN3-4") (pin "10") (pinfunction "10_10") (pintype "passive"))
    )
    (net (code "108") (name "Net-(IC14A-2D)") (class "Default")
      (node (ref "IC14") (pin "4") (pinfunction "2D_4") (pintype "input"))
      (node (ref "IN3-4") (pin "12") (pinfunction "12_12") (pintype "passive"))
    )
    (net (code "109") (name "Net-(IC14A-3D)") (class "Default")
      (node (ref "IC14") (pin "7") (pinfunction "3D_7") (pintype "input"))
      (node (ref "IN3-4") (pin "14") (pinfunction "14_14") (pintype "passive"))
    )
    (net (code "110") (name "Net-(IC14A-4D)") (class "Default")
      (node (ref "IC14") (pin "8") (pinfunction "4D_8") (pintype "input"))
      (node (ref "IN3-4") (pin "16") (pinfunction "16_16") (pintype "passive"))
    )
    (net (code "111") (name "Net-(IC14A-5D)") (class "Default")
      (node (ref "IC14") (pin "13") (pinfunction "5D_13") (pintype "input"))
      (node (ref "IN3-4") (pin "9") (pinfunction "9_9") (pintype "passive"))
    )
    (net (code "112") (name "Net-(IC14A-6D)") (class "Default")
      (node (ref "IC14") (pin "14") (pinfunction "6D_14") (pintype "input"))
      (node (ref "IN3-4") (pin "11") (pinfunction "11_11") (pintype "passive"))
    )
    (net (code "113") (name "Net-(IC14A-7D)") (class "Default")
      (node (ref "IC14") (pin "17") (pinfunction "7D_17") (pintype "input"))
      (node (ref "IN3-4") (pin "13") (pinfunction "13_13") (pintype "passive"))
    )
    (net (code "114") (name "Net-(IC14A-8D)") (class "Default")
      (node (ref "IC14") (pin "18") (pinfunction "8D_18") (pintype "input"))
      (node (ref "IN3-4") (pin "15") (pinfunction "15_15") (pintype "passive"))
    )
    (net (code "115") (name "Net-(IC15A-1D)") (class "Default")
      (node (ref "IC15") (pin "3") (pinfunction "1D_3") (pintype "input"))
      (node (ref "IN5-6") (pin "2") (pinfunction "2_2") (pintype "passive"))
    )
    (net (code "116") (name "Net-(IC15A-2D)") (class "Default")
      (node (ref "IC15") (pin "4") (pinfunction "2D_4") (pintype "input"))
      (node (ref "IN5-6") (pin "4") (pinfunction "4_4") (pintype "passive"))
    )
    (net (code "117") (name "Net-(IC15A-3D)") (class "Default")
      (node (ref "IC15") (pin "7") (pinfunction "3D_7") (pintype "input"))
      (node (ref "IN5-6") (pin "6") (pinfunction "6_6") (pintype "passive"))
    )
    (net (code "118") (name "Net-(IC15A-4D)") (class "Default")
      (node (ref "IC15") (pin "8") (pinfunction "4D_8") (pintype "input"))
      (node (ref "IN5-6") (pin "8") (pinfunction "8_8") (pintype "passive"))
    )
    (net (code "119") (name "Net-(IC15A-5D)") (class "Default")
      (node (ref "IC15") (pin "13") (pinfunction "5D_13") (pintype "input"))
      (node (ref "IN5-6") (pin "1") (pinfunction "1_1") (pintype "passive"))
    )
    (net (code "120") (name "Net-(IC15A-6D)") (class "Default")
      (node (ref "IC15") (pin "14") (pinfunction "6D_14") (pintype "input"))
      (node (ref "IN5-6") (pin "3") (pinfunction "3_3") (pintype "passive"))
    )
    (net (code "121") (name "Net-(IC15A-7D)") (class "Default")
      (node (ref "IC15") (pin "17") (pinfunction "7D_17") (pintype "input"))
      (node (ref "IN5-6") (pin "5") (pinfunction "5_5") (pintype "passive"))
    )
    (net (code "122") (name "Net-(IC15A-8D)") (class "Default")
      (node (ref "IC15") (pin "18") (pinfunction "8D_18") (pintype "input"))
      (node (ref "IN5-6") (pin "7") (pinfunction "7_7") (pintype "passive"))
    )
    (net (code "123") (name "Net-(IC16A-1D)") (class "Default")
      (node (ref "IC16") (pin "3") (pinfunction "1D_3") (pintype "input"))
      (node (ref "IN5-6") (pin "10") (pinfunction "10_10") (pintype "passive"))
    )
    (net (code "124") (name "Net-(IC16A-2D)") (class "Default")
      (node (ref "IC16") (pin "4") (pinfunction "2D_4") (pintype "input"))
      (node (ref "IN5-6") (pin "12") (pinfunction "12_12") (pintype "passive"))
    )
    (net (code "125") (name "Net-(IC16A-3D)") (class "Default")
      (node (ref "IC16") (pin "7") (pinfunction "3D_7") (pintype "input"))
      (node (ref "IN5-6") (pin "14") (pinfunction "14_14") (pintype "passive"))
    )
    (net (code "126") (name "Net-(IC16A-4D)") (class "Default")
      (node (ref "IC16") (pin "8") (pinfunction "4D_8") (pintype "input"))
      (node (ref "IN5-6") (pin "16") (pinfunction "16_16") (pintype "passive"))
    )
    (net (code "127") (name "Net-(IC16A-5D)") (class "Default")
      (node (ref "IC16") (pin "13") (pinfunction "5D_13") (pintype "input"))
      (node (ref "IN5-6") (pin "9") (pinfunction "9_9") (pintype "passive"))
    )
    (net (code "128") (name "Net-(IC16A-6D)") (class "Default")
      (node (ref "IC16") (pin "14") (pinfunction "6D_14") (pintype "input"))
      (node (ref "IN5-6") (pin "11") (pinfunction "11_11") (pintype "passive"))
    )
    (net (code "129") (name "Net-(IC16A-7D)") (class "Default")
      (node (ref "IC16") (pin "17") (pinfunction "7D_17") (pintype "input"))
      (node (ref "IN5-6") (pin "13") (pinfunction "13_13") (pintype "passive"))
    )
    (net (code "130") (name "Net-(IC16A-8D)") (class "Default")
      (node (ref "IC16") (pin "18") (pinfunction "8D_18") (pintype "input"))
      (node (ref "IN5-6") (pin "15") (pinfunction "15_15") (pintype "passive"))
    )
    (net (code "131") (name "OSEL") (class "Default")
      (node (ref "IC10") (pin "18") (pinfunction "G1_18") (pintype "input"))
      (node (ref "JP1") (pin "3") (pinfunction "3_3") (pintype "passive"))
    )
    (net (code "132") (name "OUT00") (class "Default")
      (node (ref "IC1") (pin "11") (pinfunction "CLK_11") (pintype "input"))
      (node (ref "IC10") (pin "1") (pinfunction "0_1") (pintype "output"))
    )
    (net (code "133") (name "OUT01") (class "Default")
      (node (ref "IC10") (pin "2") (pinfunction "1_2") (pintype "output"))
      (node (ref "IC2") (pin "11") (pinfunction "CLK_11") (pintype "input"))
    )
    (net (code "134") (name "OUT02") (class "Default")
      (node (ref "IC10") (pin "3") (pinfunction "2_3") (pintype "output"))
      (node (ref "IC3") (pin "11") (pinfunction "CLK_11") (pintype "input"))
    )
    (net (code "135") (name "OUT03") (class "Default")
      (node (ref "IC10") (pin "4") (pinfunction "3_4") (pintype "output"))
      (node (ref "IC4") (pin "11") (pinfunction "CLK_11") (pintype "input"))
    )
    (net (code "136") (name "OUT04") (class "Default")
      (node (ref "IC10") (pin "5") (pinfunction "4_5") (pintype "output"))
      (node (ref "IC5") (pin "11") (pinfunction "CLK_11") (pintype "input"))
    )
    (net (code "137") (name "OUT05") (class "Default")
      (node (ref "IC10") (pin "6") (pinfunction "5_6") (pintype "output"))
      (node (ref "IC6") (pin "11") (pinfunction "CLK_11") (pintype "input"))
    )
    (net (code "138") (name "OUT06") (class "Default")
      (node (ref "IC10") (pin "7") (pinfunction "6_7") (pintype "output"))
      (node (ref "IC7") (pin "11") (pinfunction "CLK_11") (pintype "input"))
    )
    (net (code "139") (name "OUT07") (class "Default")
      (node (ref "IC10") (pin "8") (pinfunction "7_8") (pintype "output"))
      (node (ref "IC8") (pin "11") (pinfunction "CLK_11") (pintype "input"))
    )
    (net (code "140") (name "OUT08") (class "Default")
      (node (ref "IC10") (pin "9") (pinfunction "8_9") (pintype "output"))
    )
    (net (code "141") (name "OUT09") (class "Default")
      (node (ref "IC10") (pin "10") (pinfunction "9_10") (pintype "output"))
    )
    (net (code "142") (name "OUT10") (class "Default")
      (node (ref "IC10") (pin "11") (pinfunction "10_11") (pintype "output"))
    )
    (net (code "143") (name "OUT11") (class "Default")
      (node (ref "IC10") (pin "13") (pinfunction "11_13") (pintype "output"))
    )
    (net (code "144") (name "OUT12") (class "Default")
      (node (ref "IC10") (pin "14") (pinfunction "12_14") (pintype "output"))
    )
    (net (code "145") (name "OUT13") (class "Default")
      (node (ref "IC10") (pin "15") (pinfunction "13_15") (pintype "output"))
    )
    (net (code "146") (name "OUT14") (class "Default")
      (node (ref "IC10") (pin "16") (pinfunction "14_16") (pintype "output"))
    )
    (net (code "147") (name "OUT15") (class "Default")
      (node (ref "IC10") (pin "17") (pinfunction "15_17") (pintype "output"))
    )
    (net (code "148") (name "PIA-A0") (class "Default")
      (node (ref "CORE-IO") (pin "1") (pinfunction "1_1") (pintype "passive"))
      (node (ref "IC1") (pin "3") (pinfunction "1D_3") (pintype "input"))
      (node (ref "IC11") (pin "2") (pinfunction "1Q_2") (pintype "tri_state"))
      (node (ref "IC12") (pin "2") (pinfunction "1Q_2") (pintype "tri_state"))
      (node (ref "IC13") (pin "2") (pinfunction "1Q_2") (pintype "tri_state"))
      (node (ref "IC14") (pin "2") (pinfunction "1Q_2") (pintype "tri_state"))
      (node (ref "IC15") (pin "2") (pinfunction "1Q_2") (pintype "tri_state"))
      (node (ref "IC16") (pin "2") (pinfunction "1Q_2") (pintype "tri_state"))
      (node (ref "IC2") (pin "3") (pinfunction "1D_3") (pintype "input"))
      (node (ref "IC3") (pin "3") (pinfunction "1D_3") (pintype "input"))
      (node (ref "IC4") (pin "3") (pinfunction "1D_3") (pintype "input"))
      (node (ref "IC5") (pin "3") (pinfunction "1D_3") (pintype "input"))
      (node (ref "IC6") (pin "3") (pinfunction "1D_3") (pintype "input"))
      (node (ref "IC7") (pin "3") (pinfunction "1D_3") (pintype "input"))
      (node (ref "IC8") (pin "3") (pinfunction "1D_3") (pintype "input"))
    )
    (net (code "149") (name "PIA-A1") (class "Default")
      (node (ref "CORE-IO") (pin "2") (pinfunction "2_2") (pintype "passive"))
      (node (ref "IC1") (pin "4") (pinfunction "2D_4") (pintype "input"))
      (node (ref "IC11") (pin "5") (pinfunction "2Q_5") (pintype "tri_state"))
      (node (ref "IC12") (pin "5") (pinfunction "2Q_5") (pintype "tri_state"))
      (node (ref "IC13") (pin "5") (pinfunction "2Q_5") (pintype "tri_state"))
      (node (ref "IC14") (pin "5") (pinfunction "2Q_5") (pintype "tri_state"))
      (node (ref "IC15") (pin "5") (pinfunction "2Q_5") (pintype "tri_state"))
      (node (ref "IC16") (pin "5") (pinfunction "2Q_5") (pintype "tri_state"))
      (node (ref "IC2") (pin "4") (pinfunction "2D_4") (pintype "input"))
      (node (ref "IC3") (pin "4") (pinfunction "2D_4") (pintype "input"))
      (node (ref "IC4") (pin "4") (pinfunction "2D_4") (pintype "input"))
      (node (ref "IC5") (pin "4") (pinfunction "2D_4") (pintype "input"))
      (node (ref "IC6") (pin "4") (pinfunction "2D_4") (pintype "input"))
      (node (ref "IC7") (pin "4") (pinfunction "2D_4") (pintype "input"))
      (node (ref "IC8") (pin "4") (pinfunction "2D_4") (pintype "input"))
    )
    (net (code "150") (name "PIA-A2") (class "Default")
      (node (ref "CORE-IO") (pin "3") (pinfunction "3_3") (pintype "passive"))
      (node (ref "IC1") (pin "7") (pinfunction "3D_7") (pintype "input"))
      (node (ref "IC11") (pin "6") (pinfunction "3Q_6") (pintype "tri_state"))
      (node (ref "IC12") (pin "6") (pinfunction "3Q_6") (pintype "tri_state"))
      (node (ref "IC13") (pin "6") (pinfunction "3Q_6") (pintype "tri_state"))
      (node (ref "IC14") (pin "6") (pinfunction "3Q_6") (pintype "tri_state"))
      (node (ref "IC15") (pin "6") (pinfunction "3Q_6") (pintype "tri_state"))
      (node (ref "IC16") (pin "6") (pinfunction "3Q_6") (pintype "tri_state"))
      (node (ref "IC2") (pin "7") (pinfunction "3D_7") (pintype "input"))
      (node (ref "IC3") (pin "7") (pinfunction "3D_7") (pintype "input"))
      (node (ref "IC4") (pin "7") (pinfunction "3D_7") (pintype "input"))
      (node (ref "IC5") (pin "7") (pinfunction "3D_7") (pintype "input"))
      (node (ref "IC6") (pin "7") (pinfunction "3D_7") (pintype "input"))
      (node (ref "IC7") (pin "7") (pinfunction "3D_7") (pintype "input"))
      (node (ref "IC8") (pin "7") (pinfunction "3D_7") (pintype "input"))
    )
    (net (code "151") (name "PIA-A3") (class "Default")
      (node (ref "CORE-IO") (pin "4") (pinfunction "4_4") (pintype "passive"))
      (node (ref "IC1") (pin "8") (pinfunction "4D_8") (pintype "input"))
      (node (ref "IC11") (pin "9") (pinfunction "4Q_9") (pintype "tri_state"))
      (node (ref "IC12") (pin "9") (pinfunction "4Q_9") (pintype "tri_state"))
      (node (ref "IC13") (pin "9") (pinfunction "4Q_9") (pintype "tri_state"))
      (node (ref "IC14") (pin "9") (pinfunction "4Q_9") (pintype "tri_state"))
      (node (ref "IC15") (pin "9") (pinfunction "4Q_9") (pintype "tri_state"))
      (node (ref "IC16") (pin "9") (pinfunction "4Q_9") (pintype "tri_state"))
      (node (ref "IC2") (pin "8") (pinfunction "4D_8") (pintype "input"))
      (node (ref "IC3") (pin "8") (pinfunction "4D_8") (pintype "input"))
      (node (ref "IC4") (pin "8") (pinfunction "4D_8") (pintype "input"))
      (node (ref "IC5") (pin "8") (pinfunction "4D_8") (pintype "input"))
      (node (ref "IC6") (pin "8") (pinfunction "4D_8") (pintype "input"))
      (node (ref "IC7") (pin "8") (pinfunction "4D_8") (pintype "input"))
      (node (ref "IC8") (pin "8") (pinfunction "4D_8") (pintype "input"))
    )
    (net (code "152") (name "PIA-A4") (class "Default")
      (node (ref "CORE-IO") (pin "5") (pinfunction "5_5") (pintype "passive"))
      (node (ref "IC1") (pin "13") (pinfunction "5D_13") (pintype "input"))
      (node (ref "IC11") (pin "12") (pinfunction "5Q_12") (pintype "tri_state"))
      (node (ref "IC12") (pin "12") (pinfunction "5Q_12") (pintype "tri_state"))
      (node (ref "IC13") (pin "12") (pinfunction "5Q_12") (pintype "tri_state"))
      (node (ref "IC14") (pin "12") (pinfunction "5Q_12") (pintype "tri_state"))
      (node (ref "IC15") (pin "12") (pinfunction "5Q_12") (pintype "tri_state"))
      (node (ref "IC16") (pin "12") (pinfunction "5Q_12") (pintype "tri_state"))
      (node (ref "IC2") (pin "13") (pinfunction "5D_13") (pintype "input"))
      (node (ref "IC3") (pin "13") (pinfunction "5D_13") (pintype "input"))
      (node (ref "IC4") (pin "13") (pinfunction "5D_13") (pintype "input"))
      (node (ref "IC5") (pin "13") (pinfunction "5D_13") (pintype "input"))
      (node (ref "IC6") (pin "13") (pinfunction "5D_13") (pintype "input"))
      (node (ref "IC7") (pin "13") (pinfunction "5D_13") (pintype "input"))
      (node (ref "IC8") (pin "13") (pinfunction "5D_13") (pintype "input"))
    )
    (net (code "153") (name "PIA-A5") (class "Default")
      (node (ref "CORE-IO") (pin "6") (pinfunction "6_6") (pintype "passive"))
      (node (ref "IC1") (pin "14") (pinfunction "6D_14") (pintype "input"))
      (node (ref "IC11") (pin "15") (pinfunction "6Q_15") (pintype "tri_state"))
      (node (ref "IC12") (pin "15") (pinfunction "6Q_15") (pintype "tri_state"))
      (node (ref "IC13") (pin "15") (pinfunction "6Q_15") (pintype "tri_state"))
      (node (ref "IC14") (pin "15") (pinfunction "6Q_15") (pintype "tri_state"))
      (node (ref "IC15") (pin "15") (pinfunction "6Q_15") (pintype "tri_state"))
      (node (ref "IC16") (pin "15") (pinfunction "6Q_15") (pintype "tri_state"))
      (node (ref "IC2") (pin "14") (pinfunction "6D_14") (pintype "input"))
      (node (ref "IC3") (pin "14") (pinfunction "6D_14") (pintype "input"))
      (node (ref "IC4") (pin "14") (pinfunction "6D_14") (pintype "input"))
      (node (ref "IC5") (pin "14") (pinfunction "6D_14") (pintype "input"))
      (node (ref "IC6") (pin "14") (pinfunction "6D_14") (pintype "input"))
      (node (ref "IC7") (pin "14") (pinfunction "6D_14") (pintype "input"))
      (node (ref "IC8") (pin "14") (pinfunction "6D_14") (pintype "input"))
    )
    (net (code "154") (name "PIA-A6") (class "Default")
      (node (ref "CORE-IO") (pin "7") (pinfunction "7_7") (pintype "passive"))
      (node (ref "IC1") (pin "17") (pinfunction "7D_17") (pintype "input"))
      (node (ref "IC11") (pin "16") (pinfunction "7Q_16") (pintype "tri_state"))
      (node (ref "IC12") (pin "16") (pinfunction "7Q_16") (pintype "tri_state"))
      (node (ref "IC13") (pin "16") (pinfunction "7Q_16") (pintype "tri_state"))
      (node (ref "IC14") (pin "16") (pinfunction "7Q_16") (pintype "tri_state"))
      (node (ref "IC15") (pin "16") (pinfunction "7Q_16") (pintype "tri_state"))
      (node (ref "IC16") (pin "16") (pinfunction "7Q_16") (pintype "tri_state"))
      (node (ref "IC2") (pin "17") (pinfunction "7D_17") (pintype "input"))
      (node (ref "IC3") (pin "17") (pinfunction "7D_17") (pintype "input"))
      (node (ref "IC4") (pin "17") (pinfunction "7D_17") (pintype "input"))
      (node (ref "IC5") (pin "17") (pinfunction "7D_17") (pintype "input"))
      (node (ref "IC6") (pin "17") (pinfunction "7D_17") (pintype "input"))
      (node (ref "IC7") (pin "17") (pinfunction "7D_17") (pintype "input"))
      (node (ref "IC8") (pin "17") (pinfunction "7D_17") (pintype "input"))
    )
    (net (code "155") (name "PIA-A7") (class "Default")
      (node (ref "CORE-IO") (pin "8") (pinfunction "8_8") (pintype "passive"))
      (node (ref "IC1") (pin "18") (pinfunction "8D_18") (pintype "input"))
      (node (ref "IC11") (pin "19") (pinfunction "8Q_19") (pintype "tri_state"))
      (node (ref "IC12") (pin "19") (pinfunction "8Q_19") (pintype "tri_state"))
      (node (ref "IC13") (pin "19") (pinfunction "8Q_19") (pintype "tri_state"))
      (node (ref "IC14") (pin "19") (pinfunction "8Q_19") (pintype "tri_state"))
      (node (ref "IC15") (pin "19") (pinfunction "8Q_19") (pintype "tri_state"))
      (node (ref "IC16") (pin "19") (pinfunction "8Q_19") (pintype "tri_state"))
      (node (ref "IC2") (pin "18") (pinfunction "8D_18") (pintype "input"))
      (node (ref "IC3") (pin "18") (pinfunction "8D_18") (pintype "input"))
      (node (ref "IC4") (pin "18") (pinfunction "8D_18") (pintype "input"))
      (node (ref "IC5") (pin "18") (pinfunction "8D_18") (pintype "input"))
      (node (ref "IC6") (pin "18") (pinfunction "8D_18") (pintype "input"))
      (node (ref "IC7") (pin "18") (pinfunction "8D_18") (pintype "input"))
      (node (ref "IC8") (pin "18") (pinfunction "8D_18") (pintype "input"))
    )
    (net (code "156") (name "PIA-B0") (class "Default")
      (node (ref "CORE-IO") (pin "13") (pinfunction "13_13") (pintype "passive"))
      (node (ref "IC10") (pin "23") (pinfunction "A_23") (pintype "input"))
      (node (ref "IC9") (pin "23") (pinfunction "A_23") (pintype "input"))
    )
    (net (code "157") (name "PIA-B1") (class "Default")
      (node (ref "CORE-IO") (pin "14") (pinfunction "14_14") (pintype "passive"))
      (node (ref "IC10") (pin "22") (pinfunction "B_22") (pintype "input"))
      (node (ref "IC9") (pin "22") (pinfunction "B_22") (pintype "input"))
    )
    (net (code "158") (name "PIA-B2") (class "Default")
      (node (ref "CORE-IO") (pin "15") (pinfunction "15_15") (pintype "passive"))
      (node (ref "IC10") (pin "21") (pinfunction "C_21") (pintype "input"))
      (node (ref "IC9") (pin "21") (pinfunction "C_21") (pintype "input"))
    )
    (net (code "159") (name "PIA-B3") (class "Default")
      (node (ref "CORE-IO") (pin "16") (pinfunction "16_16") (pintype "passive"))
      (node (ref "IC10") (pin "20") (pinfunction "D_20") (pintype "input"))
      (node (ref "IC9") (pin "20") (pinfunction "D_20") (pintype "input"))
    )
    (net (code "160") (name "PIA-B4") (class "Default")
      (node (ref "CORE-IO") (pin "17") (pinfunction "17_17") (pintype "passive"))
      (node (ref "JP1") (pin "1") (pinfunction "1_1") (pintype "passive"))
    )
    (net (code "161") (name "PIA-B5") (class "Default")
      (node (ref "CORE-IO") (pin "18") (pinfunction "18_18") (pintype "passive"))
      (node (ref "JP1") (pin "2") (pinfunction "2_2") (pintype "passive"))
    )
    (net (code "162") (name "PIA-B6") (class "Default")
      (node (ref "CORE-IO") (pin "19") (pinfunction "19_19") (pintype "passive"))
      (node (ref "JP1") (pin "5") (pinfunction "5_5") (pintype "passive"))
    )
    (net (code "163") (name "PIA-B7") (class "Default")
      (node (ref "CORE-IO") (pin "20") (pinfunction "20_20") (pintype "passive"))
      (node (ref "JP1") (pin "6") (pinfunction "6_6") (pintype "passive"))
    )
    (net (code "164") (name "VCC") (class "Default")
      (node (ref "BYP1") (pin "1") (pinfunction "1_1") (pintype "passive"))
      (node (ref "BYP10") (pin "1") (pinfunction "1_1") (pintype "passive"))
      (node (ref "BYP11") (pin "1") (pinfunction "1_1") (pintype "passive"))
      (node (ref "BYP12") (pin "1") (pinfunction "1_1") (pintype "passive"))
      (node (ref "BYP13") (pin "1") (pinfunction "1_1") (pintype "passive"))
      (node (ref "BYP14") (pin "1") (pinfunction "1_1") (pintype "passive"))
      (node (ref "BYP15") (pin "1") (pinfunction "1_1") (pintype "passive"))
      (node (ref "BYP16") (pin "1") (pinfunction "1_1") (pintype "passive"))
      (node (ref "BYP17") (pin "1") (pinfunction "1_1") (pintype "passive"))
      (node (ref "BYP2") (pin "1") (pinfunction "1_1") (pintype "passive"))
      (node (ref "BYP3") (pin "1") (pinfunction "1_1") (pintype "passive"))
      (node (ref "BYP4") (pin "1") (pinfunction "1_1") (pintype "passive"))
      (node (ref "BYP5") (pin "1") (pinfunction "1_1") (pintype "passive"))
      (node (ref "BYP6") (pin "1") (pinfunction "1_1") (pintype "passive"))
      (node (ref "BYP7") (pin "1") (pinfunction "1_1") (pintype "passive"))
      (node (ref "BYP8") (pin "1") (pinfunction "1_1") (pintype "passive"))
      (node (ref "BYP9") (pin "1") (pinfunction "1_1") (pintype "passive"))
      (node (ref "CORE-IO") (pin "11") (pinfunction "11_11") (pintype "passive"))
      (node (ref "CORE-IO") (pin "12") (pinfunction "12_12") (pintype "passive"))
      (node (ref "IC11") (pin "11") (pinfunction "ENC_11") (pintype "input"))
      (node (ref "IC12") (pin "11") (pinfunction "ENC_11") (pintype "input"))
      (node (ref "IC13") (pin "11") (pinfunction "ENC_11") (pintype "input"))
      (node (ref "IC14") (pin "11") (pinfunction "ENC_11") (pintype "input"))
      (node (ref "IC15") (pin "11") (pinfunction "ENC_11") (pintype "input"))
      (node (ref "IC16") (pin "11") (pinfunction "ENC_11") (pintype "input"))
    )
  )
)
